# nose_thermo.net
KiCad netlist of a schematic drawn in Altium Designer
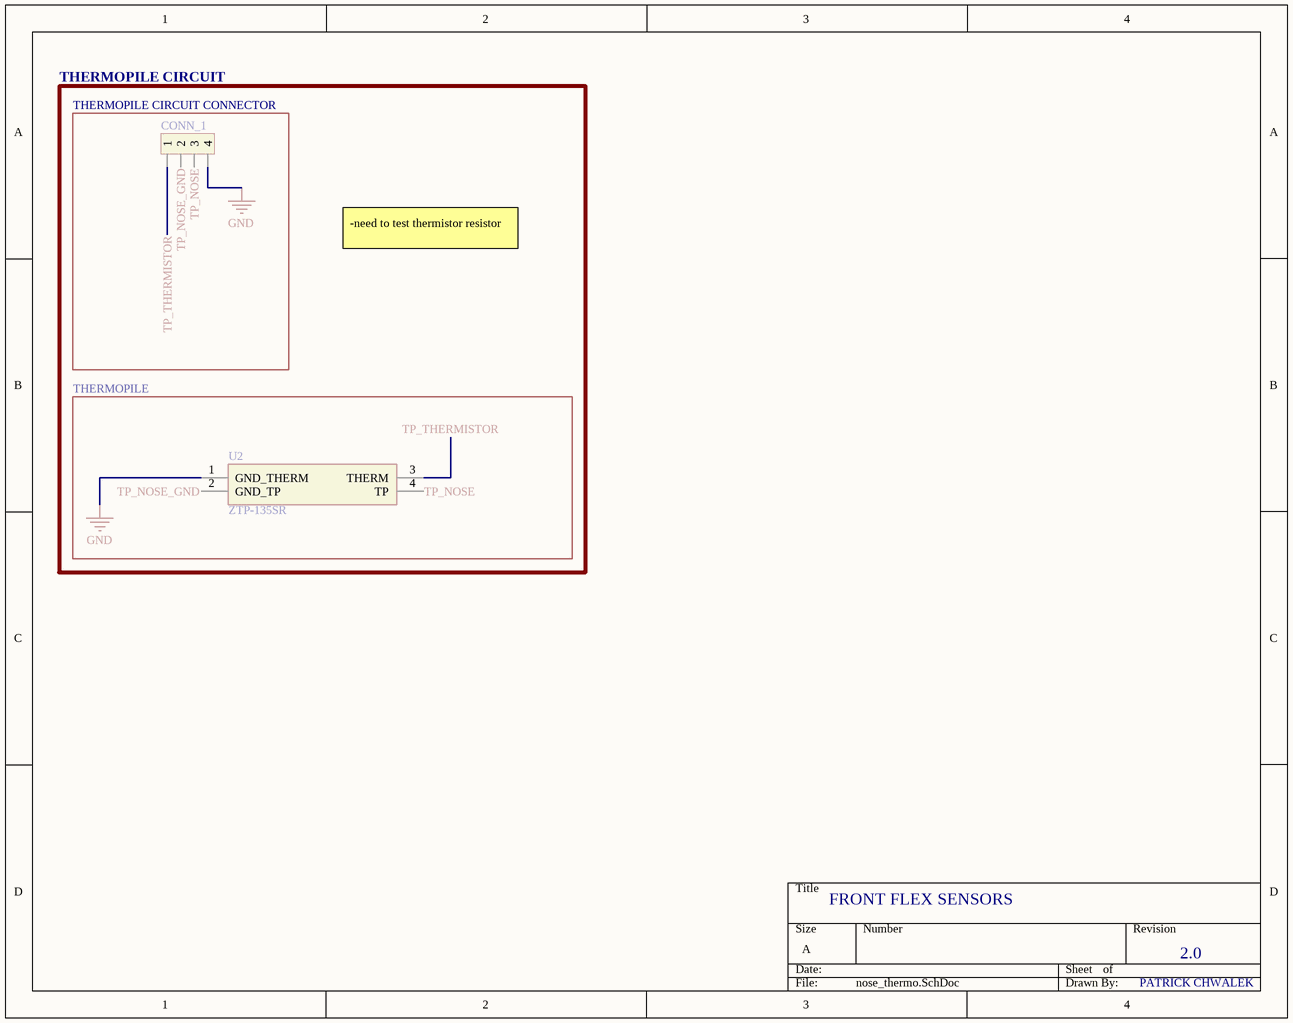
[diagram p0: nose_thermo.SchDoc]

(export (version "E")
  (design (tool "Eeschema 10.0.6"))
  (components
    (comp (ref "CONN_1")
      (value "THERMO")
      (footprint "4_pos_1mm_header")
      (libsource (lib "schematic_components") (part "4_pin_1mm_header"))
    )
    (comp (ref "U2")
      (value "ZTP-135SR")
      (footprint "ZTP-135SR")
      (description "Undefined or Miscellaneous")
      (fields (field (name "MOUSER PART NUMBER") "527-ZTP-135SR"))
      (libsource (lib "SamacSys") (part "ZTP-135SR"))
    )
  )
  (nets
    (net (code "1") (name "/TP_NOSE") (class "Default")
      (node (ref "CONN_1") (pin "3") (pinfunction "3_3") (pintype "passive"))
      (node (ref "U2") (pin "4") (pinfunction "TP_4") (pintype "passive"))
    )
    (net (code "2") (name "/TP_NOSE_GND") (class "Default")
      (node (ref "CONN_1") (pin "2") (pinfunction "2_2") (pintype "passive"))
      (node (ref "U2") (pin "2") (pinfunction "GND_TP_2") (pintype "passive"))
    )
    (net (code "3") (name "/TP_THERMISTOR") (class "Default")
      (node (ref "CONN_1") (pin "1") (pinfunction "1_1") (pintype "passive"))
      (node (ref "U2") (pin "3") (pinfunction "THERM_3") (pintype "passive"))
    )
    (net (code "4") (name "GND") (class "Default")
      (node (ref "CONN_1") (pin "4") (pinfunction "4_4") (pintype "passive"))
      (node (ref "U2") (pin "1") (pinfunction "GND_THERM_1") (pintype "passive"))
    )
  )
)
